# MOUNTING_HOLE.net
KiCad netlist of a schematic drawn in Altium Designer
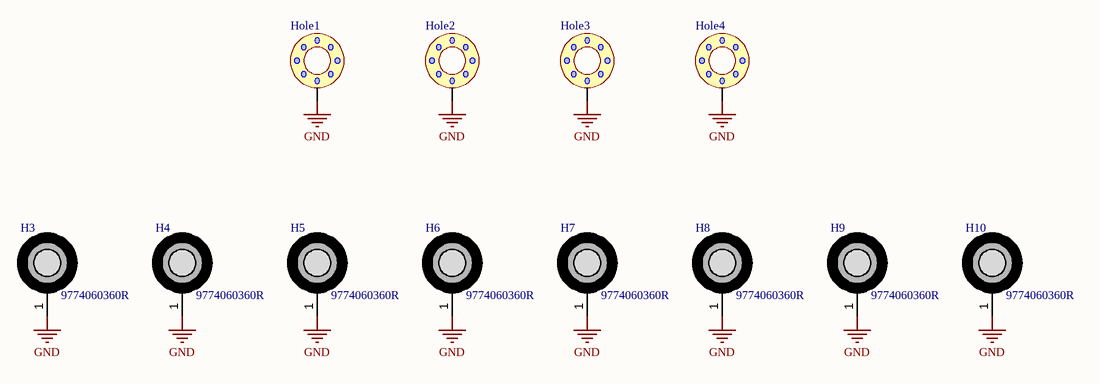
[diagram p0: MOUNTING_HOLE.SchDoc]

(export (version "E")
  (design (tool "Eeschema 10.0.6"))
  (components
    (comp (ref "H3")
      (value "9774060360R")
      (footprint "M4.4")
      (description "WA-SMSI SMT Steel Spacer with\r\ninternal Thread")
      (libsource (lib "IFBschelib") (part "M4.4"))
    )
    (comp (ref "H4")
      (value "9774060360R")
      (footprint "M4.4")
      (description "WA-SMSI SMT Steel Spacer with\r\ninternal Thread")
      (libsource (lib "IFBschelib") (part "M4.4"))
    )
    (comp (ref "H5")
      (value "9774060360R")
      (footprint "M4.4")
      (description "WA-SMSI SMT Steel Spacer with\r\ninternal Thread")
      (libsource (lib "IFBschelib") (part "M4.4"))
    )
    (comp (ref "H6")
      (value "9774060360R")
      (footprint "M4.4")
      (description "WA-SMSI SMT Steel Spacer with\r\ninternal Thread")
      (libsource (lib "IFBschelib") (part "M4.4"))
    )
    (comp (ref "H7")
      (value "9774060360R")
      (footprint "M4.4")
      (description "WA-SMSI SMT Steel Spacer with\r\ninternal Thread")
      (libsource (lib "IFBschelib") (part "M4.4"))
    )
    (comp (ref "H8")
      (value "9774060360R")
      (footprint "M4.4")
      (description "WA-SMSI SMT Steel Spacer with\r\ninternal Thread")
      (libsource (lib "IFBschelib") (part "M4.4"))
    )
    (comp (ref "H9")
      (value "9774060360R")
      (footprint "M4.4")
      (description "WA-SMSI SMT Steel Spacer with\r\ninternal Thread")
      (libsource (lib "IFBschelib") (part "M4.4"))
    )
    (comp (ref "H10")
      (value "9774060360R")
      (footprint "M4.4")
      (description "WA-SMSI SMT Steel Spacer with\r\ninternal Thread")
      (libsource (lib "IFBschelib") (part "M4.4"))
    )
    (comp (ref "Hole1")
      (value "hole_space")
      (footprint "HEX-M3_NoVia")
      (libsource (lib "IFBschelib") (part "hole_space"))
    )
    (comp (ref "Hole2")
      (value "hole_space")
      (footprint "HEX-M3_NoVia")
      (libsource (lib "IFBschelib") (part "hole_space"))
    )
    (comp (ref "Hole3")
      (value "hole_space")
      (footprint "HEX-M3_NoVia")
      (libsource (lib "IFBschelib") (part "hole_space"))
    )
    (comp (ref "Hole4")
      (value "hole_space")
      (footprint "HEX-M3_NoVia")
      (libsource (lib "IFBschelib") (part "hole_space"))
    )
  )
  (nets
    (net (code "1") (name "GND") (class "Default")
      (node (ref "H10") (pin "1") (pinfunction "1_1") (pintype "passive"))
      (node (ref "H3") (pin "1") (pinfunction "1_1") (pintype "passive"))
      (node (ref "H4") (pin "1") (pinfunction "1_1") (pintype "passive"))
      (node (ref "H5") (pin "1") (pinfunction "1_1") (pintype "passive"))
      (node (ref "H6") (pin "1") (pinfunction "1_1") (pintype "passive"))
      (node (ref "H7") (pin "1") (pinfunction "1_1") (pintype "passive"))
      (node (ref "H8") (pin "1") (pinfunction "1_1") (pintype "passive"))
      (node (ref "H9") (pin "1") (pinfunction "1_1") (pintype "passive"))
      (node (ref "Hole1") (pin "1") (pinfunction "1_1") (pintype "passive"))
      (node (ref "Hole2") (pin "1") (pinfunction "1_1") (pintype "passive"))
      (node (ref "Hole3") (pin "1") (pinfunction "1_1") (pintype "passive"))
      (node (ref "Hole4") (pin "1") (pinfunction "1_1") (pintype "passive"))
    )
  )
)
